# ComplexLEDs_copy.net
KiCad netlist of a schematic drawn in EAGLE
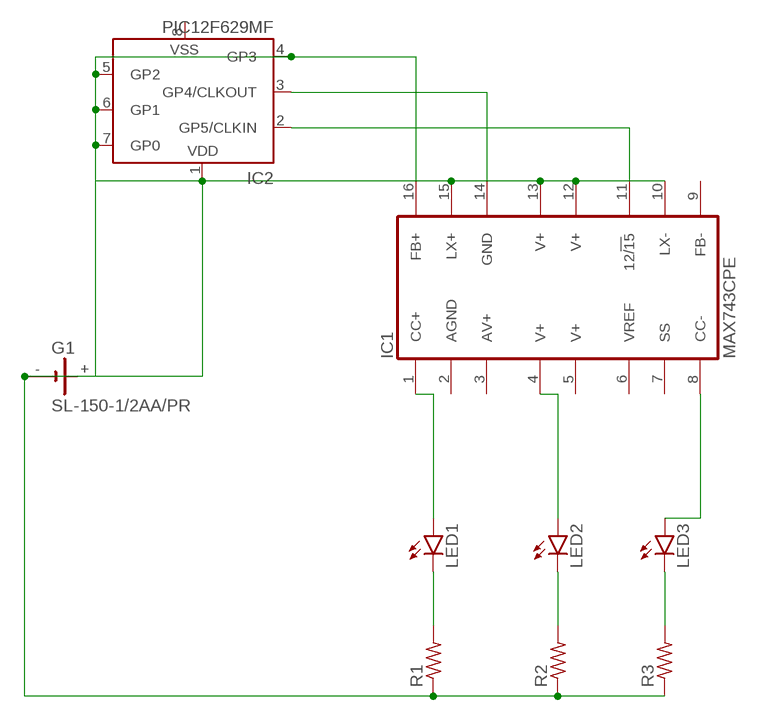
[diagram p0: schematic, sheet 1]

(export (version "E")
  (design (tool "Eeschema 10.0.6"))
  (components
    (comp (ref "G1")
      (value "SL-150-1/2AA/PR")
      (footprint "eagle-import:SL-150-1_2AA_PR")
      (libsource (lib "eagle-import") (part "SL-150-1/2AA/PR"))
    )
    (comp (ref "IC1")
      (value "MAX743CPE")
      (footprint "eagle-import:DIL16")
      (fields (field (name "MF") "MAXIM"))
      (libsource (lib "eagle-import") (part "MAX743CPE"))
    )
    (comp (ref "IC2")
      (value "PIC12F629MF")
      (footprint "eagle-import:DFN-S")
      (fields (field (name "MF") "MICROCHIP") (field (name "MPN") "PIC12F629-I/MD"))
      (libsource (lib "eagle-import") (part "PIC12F6MF29"))
    )
    (comp (ref "LED1")
      (value "LED5MM")
      (footprint "eagle-import:LED5MM")
      (libsource (lib "eagle-import") (part "LED5MM"))
    )
    (comp (ref "LED2")
      (value "LED5MM")
      (footprint "eagle-import:LED5MM")
      (libsource (lib "eagle-import") (part "LED5MM"))
    )
    (comp (ref "LED3")
      (value "LED5MM")
      (footprint "eagle-import:LED5MM")
      (libsource (lib "eagle-import") (part "LED5MM"))
    )
    (comp (ref "R1")
      (value "R-US_0309/10")
      (footprint "eagle-import:0309_10")
      (libsource (lib "eagle-import") (part "R-US_0309/10"))
    )
    (comp (ref "R2")
      (value "R-US_0309/10")
      (footprint "eagle-import:0309_10")
      (libsource (lib "eagle-import") (part "R-US_0309/10"))
    )
    (comp (ref "R3")
      (value "R-US_0309/10")
      (footprint "eagle-import:0309_10")
      (libsource (lib "eagle-import") (part "R-US_0309/10"))
    )
  )
  (nets
    (net (code "1") (name "/AGND") (class "Default")
      (node (ref "IC1") (pin "2") (pinfunction "AGND_2") (pintype "power_in"))
    )
    (net (code "2") (name "/VREF") (class "Default")
      (node (ref "IC1") (pin "6") (pinfunction "VREF_6") (pintype "power_in"))
    )
    (net (code "3") (name "/VSS") (class "Default")
      (node (ref "IC2") (pin "8") (pinfunction "VSS_8") (pintype "power_in"))
    )
    (net (code "4") (name "Net-(IC1-12{slash}15)") (class "Default")
      (node (ref "IC1") (pin "11") (pinfunction "12/15_11") (pintype "input"))
      (node (ref "IC2") (pin "2") (pinfunction "GP5/CLKIN_2") (pintype "bidirectional"))
    )
    (net (code "5") (name "Net-(IC1-CC+)") (class "Default")
      (node (ref "IC1") (pin "1") (pinfunction "CC+_1") (pintype "passive"))
      (node (ref "LED1") (pin "A") (pinfunction "A_A") (pintype "passive"))
    )
    (net (code "6") (name "Net-(IC1-CC-)") (class "Default")
      (node (ref "IC1") (pin "8") (pinfunction "CC-_8") (pintype "passive"))
      (node (ref "LED3") (pin "A") (pinfunction "A_A") (pintype "passive"))
    )
    (net (code "7") (name "Net-(IC1-FB+)") (class "Default")
      (node (ref "G1") (pin "+") (pinfunction "+_+") (pintype "passive"))
      (node (ref "G1") (pin "-") (pinfunction "-_-") (pintype "passive"))
      (node (ref "IC1") (pin "10") (pinfunction "LX-_10") (pintype "passive"))
      (node (ref "IC1") (pin "12") (pinfunction "V+_12") (pintype "input"))
      (node (ref "IC1") (pin "13") (pinfunction "V+_13") (pintype "input"))
      (node (ref "IC1") (pin "15") (pinfunction "LX+_15") (pintype "passive"))
      (node (ref "IC1") (pin "16") (pinfunction "FB+_16") (pintype "input"))
      (node (ref "IC2") (pin "1") (pinfunction "VDD_1") (pintype "power_in"))
      (node (ref "IC2") (pin "4") (pinfunction "GP3_4") (pintype "input"))
      (node (ref "IC2") (pin "5") (pinfunction "GP2_5") (pintype "bidirectional"))
      (node (ref "IC2") (pin "6") (pinfunction "GP1_6") (pintype "bidirectional"))
      (node (ref "IC2") (pin "7") (pinfunction "GP0_7") (pintype "bidirectional"))
      (node (ref "R1") (pin "1") (pinfunction "1_1") (pintype "passive"))
      (node (ref "R2") (pin "1") (pinfunction "1_1") (pintype "passive"))
      (node (ref "R3") (pin "1") (pinfunction "1_1") (pintype "passive"))
    )
    (net (code "8") (name "Net-(IC1-GND)") (class "Default")
      (node (ref "IC1") (pin "14") (pinfunction "GND_14") (pintype "power_in"))
      (node (ref "IC2") (pin "3") (pinfunction "GP4/CLKOUT_3") (pintype "bidirectional"))
    )
    (net (code "9") (name "Net-(IC1-V+-Pad4)") (class "Default")
      (node (ref "IC1") (pin "4") (pinfunction "V+_4") (pintype "input"))
      (node (ref "LED2") (pin "A") (pinfunction "A_A") (pintype "passive"))
    )
    (net (code "10") (name "Net-(LED1-C)") (class "Default")
      (node (ref "LED1") (pin "K") (pinfunction "C_K") (pintype "passive"))
      (node (ref "R1") (pin "2") (pinfunction "2_2") (pintype "passive"))
    )
    (net (code "11") (name "Net-(LED2-C)") (class "Default")
      (node (ref "LED2") (pin "K") (pinfunction "C_K") (pintype "passive"))
      (node (ref "R2") (pin "2") (pinfunction "2_2") (pintype "passive"))
    )
    (net (code "12") (name "Net-(LED3-C)") (class "Default")
      (node (ref "LED3") (pin "K") (pinfunction "C_K") (pintype "passive"))
      (node (ref "R3") (pin "2") (pinfunction "2_2") (pintype "passive"))
    )
    (net (code "13") (name "unconnected-(IC1-AV+-Pad3)") (class "Default")
      (node (ref "IC1") (pin "3") (pinfunction "AV+_3") (pintype "input"))
    )
    (net (code "14") (name "unconnected-(IC1-FB--Pad9)") (class "Default")
      (node (ref "IC1") (pin "9") (pinfunction "FB-_9") (pintype "input"))
    )
    (net (code "15") (name "unconnected-(IC1-SS-Pad7)") (class "Default")
      (node (ref "IC1") (pin "7") (pinfunction "SS_7") (pintype "passive"))
    )
    (net (code "16") (name "unconnected-(IC1-V+-Pad5)") (class "Default")
      (node (ref "IC1") (pin "5") (pinfunction "V+_5") (pintype "input"))
    )
  )
)
